# Transponder_Proaut_V2.net
KiCad netlist of a schematic drawn in EAGLE
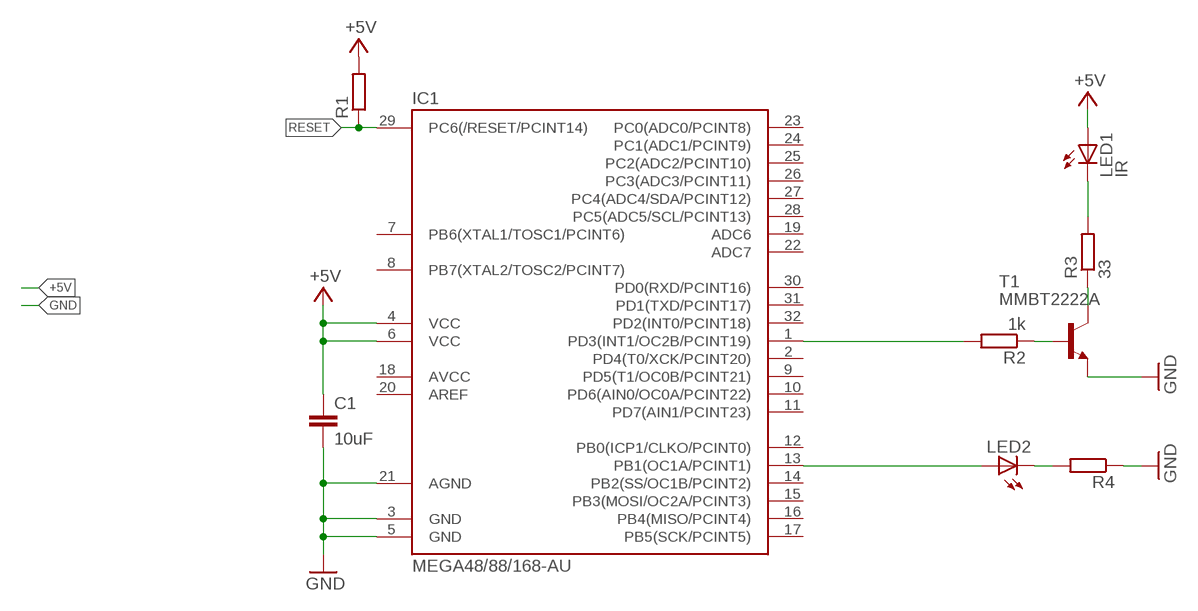
[diagram p0: schematic, sheet 1]

(export (version "E")
  (design (tool "Eeschema 10.0.6"))
  (components
    (comp (ref "C1")
      (value "10uF")
      (footprint "eagle-import:C0805")
      (libsource (lib "eagle-import") (part "C-EUC0805"))
    )
    (comp (ref "IC1")
      (value "MEGA48/88/168-AU")
      (footprint "eagle-import:TQFP32-08")
      (libsource (lib "eagle-import") (part "MEGA48/88/168-AU"))
    )
    (comp (ref "LED1")
      (value "IR")
      (footprint "eagle-import:LED5MM")
      (libsource (lib "eagle-import") (part "LED5MM"))
    )
    (comp (ref "LED2")
      (value "LEDSML1206")
      (footprint "eagle-import:SML1206")
      (libsource (lib "eagle-import") (part "LEDSML1206"))
    )
    (comp (ref "R1")
      (value "R-EU_R0805")
      (footprint "eagle-import:R0805@1")
      (libsource (lib "eagle-import") (part "R-EU_R0805"))
    )
    (comp (ref "R2")
      (value "1k")
      (footprint "eagle-import:R0805@1")
      (libsource (lib "eagle-import") (part "R-EU_R0805"))
    )
    (comp (ref "R3")
      (value "33")
      (footprint "eagle-import:R0805@1")
      (libsource (lib "eagle-import") (part "R-EU_R0805"))
    )
    (comp (ref "R4")
      (value "R-EU_R0805")
      (footprint "eagle-import:R0805@1")
      (libsource (lib "eagle-import") (part "R-EU_R0805"))
    )
    (comp (ref "T1")
      (value "MMBT2222A")
      (footprint "eagle-import:SOT23-BEC")
      (libsource (lib "eagle-import") (part "-NPN-SOT23-BECMMBT2222ALT1"))
    )
  )
  (nets
    (net (code "1") (name "+5V") (class "Default")
      (node (ref "C1") (pin "1") (pinfunction "1_1") (pintype "passive"))
      (node (ref "IC1") (pin "4") (pinfunction "VCC_4") (pintype "power_in"))
      (node (ref "IC1") (pin "6") (pinfunction "VCC_6") (pintype "power_in"))
      (node (ref "LED1") (pin "A") (pinfunction "A_A") (pintype "passive"))
      (node (ref "R1") (pin "2") (pinfunction "2_2") (pintype "passive"))
    )
    (net (code "2") (name "GND") (class "Default")
      (node (ref "C1") (pin "2") (pinfunction "2_2") (pintype "passive"))
      (node (ref "IC1") (pin "21") (pinfunction "AGND_21") (pintype "power_in"))
      (node (ref "IC1") (pin "3") (pinfunction "GND_3") (pintype "power_in"))
      (node (ref "IC1") (pin "5") (pinfunction "GND_5") (pintype "power_in"))
      (node (ref "R4") (pin "1") (pinfunction "1_1") (pintype "passive"))
      (node (ref "T1") (pin "E") (pinfunction "E_E") (pintype "passive"))
    )
    (net (code "3") (name "Net-(IC1-PB1(OC1A{slash}PCINT1))") (class "Default")
      (node (ref "IC1") (pin "13") (pinfunction "PB1(OC1A/PCINT1)_13") (pintype "bidirectional"))
      (node (ref "LED2") (pin "A") (pinfunction "A_A") (pintype "passive"))
    )
    (net (code "4") (name "Net-(IC1-PD3(INT1{slash}OC2B{slash}PCINT19))") (class "Default")
      (node (ref "IC1") (pin "1") (pinfunction "PD3(INT1/OC2B/PCINT19)_1") (pintype "bidirectional"))
      (node (ref "R2") (pin "2") (pinfunction "2_2") (pintype "passive"))
    )
    (net (code "5") (name "Net-(LED1-C)") (class "Default")
      (node (ref "LED1") (pin "K") (pinfunction "C_K") (pintype "passive"))
      (node (ref "R3") (pin "2") (pinfunction "2_2") (pintype "passive"))
    )
    (net (code "6") (name "Net-(LED2-PadC)") (class "Default")
      (node (ref "LED2") (pin "C") (pinfunction "C_C") (pintype "passive"))
      (node (ref "R4") (pin "2") (pinfunction "2_2") (pintype "passive"))
    )
    (net (code "7") (name "Net-(R2-Pad1)") (class "Default")
      (node (ref "R2") (pin "1") (pinfunction "1_1") (pintype "passive"))
      (node (ref "T1") (pin "B") (pinfunction "B_B") (pintype "passive"))
    )
    (net (code "8") (name "Net-(R3-Pad1)") (class "Default")
      (node (ref "R3") (pin "1") (pinfunction "1_1") (pintype "passive"))
      (node (ref "T1") (pin "C") (pinfunction "C_C") (pintype "passive"))
    )
    (net (code "9") (name "RESET") (class "Default")
      (node (ref "IC1") (pin "29") (pinfunction "PC6(/RESET/PCINT14)_29") (pintype "bidirectional"))
      (node (ref "R1") (pin "1") (pinfunction "1_1") (pintype "passive"))
    )
    (net (code "10") (name "unconnected-(IC1-ADC6-Pad19)") (class "Default")
      (node (ref "IC1") (pin "19") (pinfunction "ADC6_19") (pintype "passive"))
    )
    (net (code "11") (name "unconnected-(IC1-ADC7-Pad22)") (class "Default")
      (node (ref "IC1") (pin "22") (pinfunction "ADC7_22") (pintype "passive"))
    )
    (net (code "12") (name "unconnected-(IC1-AREF-Pad20)") (class "Default")
      (node (ref "IC1") (pin "20") (pinfunction "AREF_20") (pintype "passive"))
    )
    (net (code "13") (name "unconnected-(IC1-AVCC-Pad18)") (class "Default")
      (node (ref "IC1") (pin "18") (pinfunction "AVCC_18") (pintype "passive"))
    )
    (net (code "14") (name "unconnected-(IC1-PB0(ICP1{slash}CLKO{slash}PCINT0)-Pad12)") (class "Default")
      (node (ref "IC1") (pin "12") (pinfunction "PB0(ICP1/CLKO/PCINT0)_12") (pintype "bidirectional"))
    )
    (net (code "15") (name "unconnected-(IC1-PB2(SS{slash}OC1B{slash}PCINT2)-Pad14)") (class "Default")
      (node (ref "IC1") (pin "14") (pinfunction "PB2(SS/OC1B/PCINT2)_14") (pintype "bidirectional"))
    )
    (net (code "16") (name "unconnected-(IC1-PB3(MOSI{slash}OC2A{slash}PCINT3)-Pad15)") (class "Default")
      (node (ref "IC1") (pin "15") (pinfunction "PB3(MOSI/OC2A/PCINT3)_15") (pintype "bidirectional"))
    )
    (net (code "17") (name "unconnected-(IC1-PB4(MISO{slash}PCINT4)-Pad16)") (class "Default")
      (node (ref "IC1") (pin "16") (pinfunction "PB4(MISO/PCINT4)_16") (pintype "bidirectional"))
    )
    (net (code "18") (name "unconnected-(IC1-PB5(SCK{slash}PCINT5)-Pad17)") (class "Default")
      (node (ref "IC1") (pin "17") (pinfunction "PB5(SCK/PCINT5)_17") (pintype "bidirectional"))
    )
    (net (code "19") (name "unconnected-(IC1-PB6(XTAL1{slash}TOSC1{slash}PCINT6)-Pad7)") (class "Default")
      (node (ref "IC1") (pin "7") (pinfunction "PB6(XTAL1/TOSC1/PCINT6)_7") (pintype "bidirectional"))
    )
    (net (code "20") (name "unconnected-(IC1-PB7(XTAL2{slash}TOSC2{slash}PCINT7)-Pad8)") (class "Default")
      (node (ref "IC1") (pin "8") (pinfunction "PB7(XTAL2/TOSC2/PCINT7)_8") (pintype "bidirectional"))
    )
    (net (code "21") (name "unconnected-(IC1-PC0(ADC0{slash}PCINT8)-Pad23)") (class "Default")
      (node (ref "IC1") (pin "23") (pinfunction "PC0(ADC0/PCINT8)_23") (pintype "bidirectional"))
    )
    (net (code "22") (name "unconnected-(IC1-PC1(ADC1{slash}PCINT9)-Pad24)") (class "Default")
      (node (ref "IC1") (pin "24") (pinfunction "PC1(ADC1/PCINT9)_24") (pintype "bidirectional"))
    )
    (net (code "23") (name "unconnected-(IC1-PC2(ADC2{slash}PCINT10)-Pad25)") (class "Default")
      (node (ref "IC1") (pin "25") (pinfunction "PC2(ADC2/PCINT10)_25") (pintype "bidirectional"))
    )
    (net (code "24") (name "unconnected-(IC1-PC3(ADC3{slash}PCINT11)-Pad26)") (class "Default")
      (node (ref "IC1") (pin "26") (pinfunction "PC3(ADC3/PCINT11)_26") (pintype "bidirectional"))
    )
    (net (code "25") (name "unconnected-(IC1-PC4(ADC4{slash}SDA{slash}PCINT12)-Pad27)") (class "Default")
      (node (ref "IC1") (pin "27") (pinfunction "PC4(ADC4/SDA/PCINT12)_27") (pintype "bidirectional"))
    )
    (net (code "26") (name "unconnected-(IC1-PC5(ADC5{slash}SCL{slash}PCINT13)-Pad28)") (class "Default")
      (node (ref "IC1") (pin "28") (pinfunction "PC5(ADC5/SCL/PCINT13)_28") (pintype "bidirectional"))
    )
    (net (code "27") (name "unconnected-(IC1-PD0(RXD{slash}PCINT16)-Pad30)") (class "Default")
      (node (ref "IC1") (pin "30") (pinfunction "PD0(RXD/PCINT16)_30") (pintype "bidirectional"))
    )
    (net (code "28") (name "unconnected-(IC1-PD1(TXD{slash}PCINT17)-Pad31)") (class "Default")
      (node (ref "IC1") (pin "31") (pinfunction "PD1(TXD/PCINT17)_31") (pintype "bidirectional"))
    )
    (net (code "29") (name "unconnected-(IC1-PD2(INT0{slash}PCINT18)-Pad32)") (class "Default")
      (node (ref "IC1") (pin "32") (pinfunction "PD2(INT0/PCINT18)_32") (pintype "bidirectional"))
    )
    (net (code "30") (name "unconnected-(IC1-PD4(T0{slash}XCK{slash}PCINT20)-Pad2)") (class "Default")
      (node (ref "IC1") (pin "2") (pinfunction "PD4(T0/XCK/PCINT20)_2") (pintype "bidirectional"))
    )
    (net (code "31") (name "unconnected-(IC1-PD5(T1{slash}OC0B{slash}PCINT21)-Pad9)") (class "Default")
      (node (ref "IC1") (pin "9") (pinfunction "PD5(T1/OC0B/PCINT21)_9") (pintype "bidirectional"))
    )
    (net (code "32") (name "unconnected-(IC1-PD6(AIN0{slash}OC0A{slash}PCINT22)-Pad10)") (class "Default")
      (node (ref "IC1") (pin "10") (pinfunction "PD6(AIN0/OC0A/PCINT22)_10") (pintype "bidirectional"))
    )
    (net (code "33") (name "unconnected-(IC1-PD7(AIN1{slash}PCINT23)-Pad11)") (class "Default")
      (node (ref "IC1") (pin "11") (pinfunction "PD7(AIN1/PCINT23)_11") (pintype "bidirectional"))
    )
  )
)
